# DCC-headlight-V2.net
KiCad netlist of a schematic drawn in EAGLE
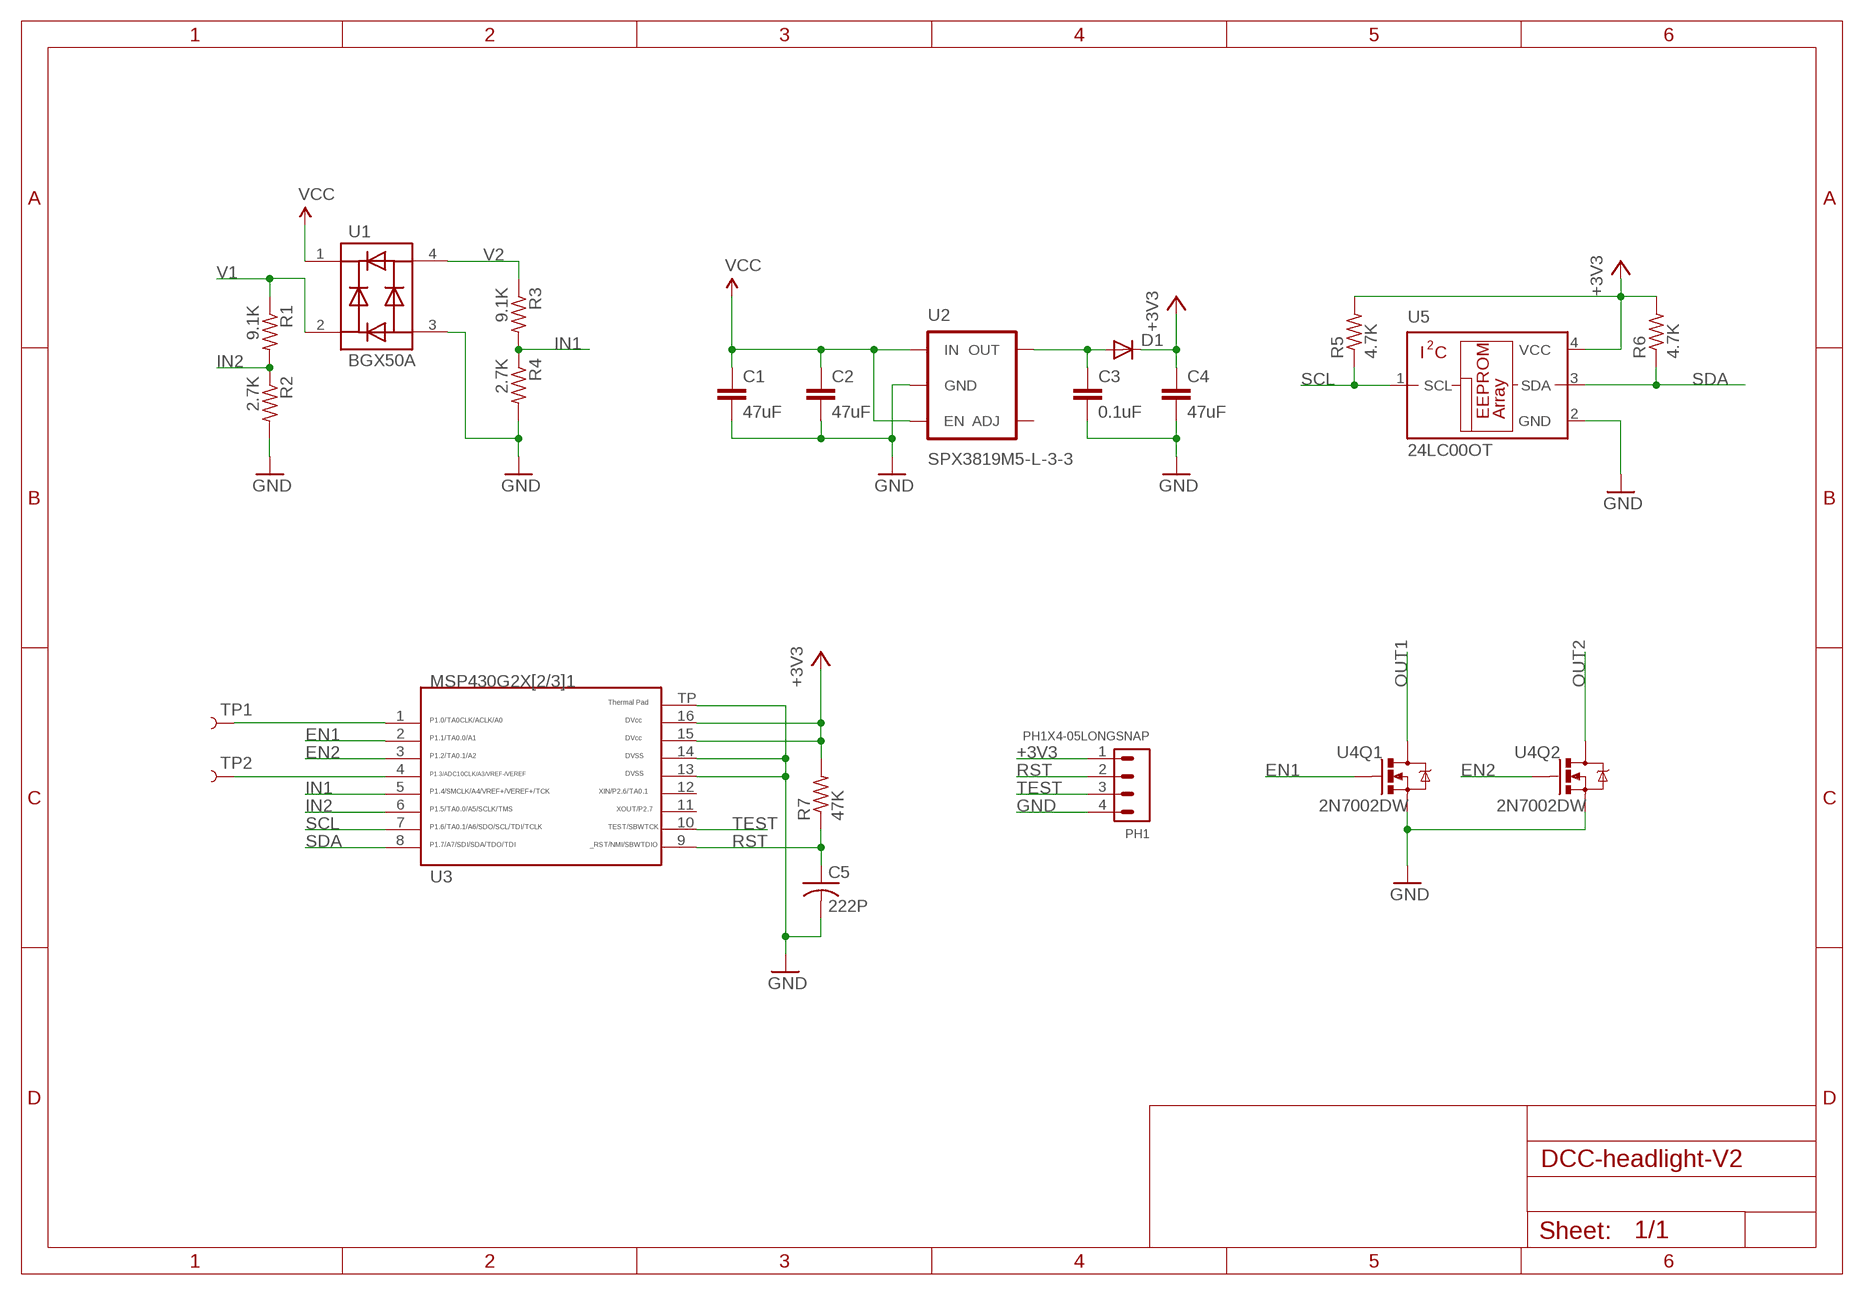
[diagram p0: schematic, sheet 1]

(export (version "E")
  (design (tool "Eeschema 10.0.6"))
  (components
    (comp (ref "C1")
      (value "47uF")
      (footprint "eagle-import:0402-CAP")
      (libsource (lib "eagle-import") (part "CAP0402-CAP"))
    )
    (comp (ref "C2")
      (value "47uF")
      (footprint "eagle-import:0402-CAP")
      (libsource (lib "eagle-import") (part "CAP0402-CAP"))
    )
    (comp (ref "C3")
      (value "0.1uF")
      (footprint "eagle-import:0402-CAP")
      (libsource (lib "eagle-import") (part "CAP0402-CAP"))
    )
    (comp (ref "C4")
      (value "47uF")
      (footprint "eagle-import:0402-CAP")
      (libsource (lib "eagle-import") (part "CAP0402-CAP"))
    )
    (comp (ref "C5")
      (value "222P")
      (footprint "eagle-import:C0402")
      (libsource (lib "eagle-import") (part "C-USC0402"))
    )
    (comp (ref "D1")
      (value "DIODE-SOD523")
      (footprint "eagle-import:SOD523")
      (libsource (lib "eagle-import") (part "DIODE-SOD523"))
    )
    (comp (ref "PH1")
      (value "PH1X4-05LONGSNAP")
      (footprint "eagle-import:PHLS005-1-4")
      (libsource (lib "eagle-import") (part "PH1X4-05LONGSNAP"))
    )
    (comp (ref "R1")
      (value "9.1K")
      (footprint "eagle-import:R0402")
      (libsource (lib "eagle-import") (part "R-US_R0402"))
    )
    (comp (ref "R2")
      (value "2.7K")
      (footprint "eagle-import:R0402")
      (libsource (lib "eagle-import") (part "R-US_R0402"))
    )
    (comp (ref "R3")
      (value "9.1K")
      (footprint "eagle-import:R0402")
      (libsource (lib "eagle-import") (part "R-US_R0402"))
    )
    (comp (ref "R4")
      (value "2.7K")
      (footprint "eagle-import:R0402")
      (libsource (lib "eagle-import") (part "R-US_R0402"))
    )
    (comp (ref "R5")
      (value "4.7K")
      (footprint "eagle-import:R0402")
      (libsource (lib "eagle-import") (part "R-US_R0402"))
    )
    (comp (ref "R6")
      (value "4.7K")
      (footprint "eagle-import:R0402")
      (libsource (lib "eagle-import") (part "R-US_R0402"))
    )
    (comp (ref "R7")
      (value "47K")
      (footprint "eagle-import:R0402")
      (libsource (lib "eagle-import") (part "R-US_R0402"))
    )
    (comp (ref "TP1")
      (value "TEST-POINT3")
      (footprint "eagle-import:PAD.03X.03")
      (libsource (lib "eagle-import") (part "TEST-POINT3"))
    )
    (comp (ref "TP2")
      (value "TEST-POINT3")
      (footprint "eagle-import:PAD.03X.03")
      (libsource (lib "eagle-import") (part "TEST-POINT3"))
    )
    (comp (ref "U1")
      (value "BGX50A")
      (footprint "eagle-import:SOT143")
      (libsource (lib "eagle-import") (part "BGX50A"))
    )
    (comp (ref "U2")
      (value "SPX3819M5-L-3-3")
      (footprint "eagle-import:SOT23-5")
      (libsource (lib "eagle-import") (part "AP2202-ADJ"))
    )
    (comp (ref "U3")
      (value "G2X[2/3]1---RSA16")
      (footprint "eagle-import:RSA16")
      (libsource (lib "eagle-import") (part "G2X[2/3]1---RSA16"))
    )
    (comp (ref "U4")
      (value "2N7002DW")
      (footprint "eagle-import:SOT363")
      (libsource (lib "eagle-import") (part "2N7002DW"))
    )
    (comp (ref "U5")
      (value "24LC00OT")
      (footprint "eagle-import:SOT23-5L")
      (fields (field (name "MF") "MICROCHIP") (field (name "MPN") "24LC00T-I/OT"))
      (libsource (lib "eagle-import") (part "2400OTLC"))
    )
  )
  (nets
    (net (code "1") (name "+3V3") (class "Default")
      (node (ref "C4") (pin "1") (pinfunction "1_1") (pintype "passive"))
      (node (ref "D1") (pin "C") (pinfunction "C_C") (pintype "passive"))
      (node (ref "PH1") (pin "1") (pinfunction "1_1") (pintype "bidirectional"))
      (node (ref "R5") (pin "2") (pinfunction "2_2") (pintype "passive"))
      (node (ref "R6") (pin "2") (pinfunction "2_2") (pintype "passive"))
      (node (ref "R7") (pin "2") (pinfunction "2_2") (pintype "passive"))
      (node (ref "U3") (pin "15") (pinfunction "15_15") (pintype "bidirectional"))
      (node (ref "U3") (pin "16") (pinfunction "16_16") (pintype "bidirectional"))
      (node (ref "U5") (pin "4") (pinfunction "VCC_4") (pintype "power_in"))
    )
    (net (code "2") (name "/EN1") (class "Default")
      (node (ref "U3") (pin "2") (pinfunction "2_2") (pintype "bidirectional"))
      (node (ref "U4") (pin "2") (pinfunction "G_2") (pintype "passive"))
    )
    (net (code "3") (name "/EN2") (class "Default")
      (node (ref "U3") (pin "3") (pinfunction "3_3") (pintype "bidirectional"))
      (node (ref "U4") (pin "5") (pinfunction "G_5") (pintype "passive"))
    )
    (net (code "4") (name "/IN1") (class "Default")
      (node (ref "R3") (pin "2") (pinfunction "2_2") (pintype "passive"))
      (node (ref "R4") (pin "1") (pinfunction "1_1") (pintype "passive"))
      (node (ref "U3") (pin "5") (pinfunction "5_5") (pintype "bidirectional"))
    )
    (net (code "5") (name "/IN2") (class "Default")
      (node (ref "R1") (pin "2") (pinfunction "2_2") (pintype "passive"))
      (node (ref "R2") (pin "1") (pinfunction "1_1") (pintype "passive"))
      (node (ref "U3") (pin "6") (pinfunction "6_6") (pintype "bidirectional"))
    )
    (net (code "6") (name "/OUT1") (class "Default")
      (node (ref "U4") (pin "6") (pinfunction "D_6") (pintype "passive"))
    )
    (net (code "7") (name "/OUT2") (class "Default")
      (node (ref "U4") (pin "3") (pinfunction "D_3") (pintype "passive"))
    )
    (net (code "8") (name "/RST") (class "Default")
      (node (ref "C5") (pin "1") (pinfunction "1_1") (pintype "passive"))
      (node (ref "PH1") (pin "2") (pinfunction "2_2") (pintype "bidirectional"))
      (node (ref "R7") (pin "1") (pinfunction "1_1") (pintype "passive"))
      (node (ref "U3") (pin "9") (pinfunction "9_9") (pintype "bidirectional"))
    )
    (net (code "9") (name "/SCL") (class "Default")
      (node (ref "R5") (pin "1") (pinfunction "1_1") (pintype "passive"))
      (node (ref "U3") (pin "7") (pinfunction "7_7") (pintype "bidirectional"))
      (node (ref "U5") (pin "1") (pinfunction "SCL_1") (pintype "input"))
    )
    (net (code "10") (name "/SDA") (class "Default")
      (node (ref "R6") (pin "1") (pinfunction "1_1") (pintype "passive"))
      (node (ref "U3") (pin "8") (pinfunction "8_8") (pintype "bidirectional"))
      (node (ref "U5") (pin "3") (pinfunction "SDA_3") (pintype "bidirectional"))
    )
    (net (code "11") (name "/TEST") (class "Default")
      (node (ref "PH1") (pin "3") (pinfunction "3_3") (pintype "bidirectional"))
      (node (ref "U3") (pin "10") (pinfunction "10_10") (pintype "bidirectional"))
    )
    (net (code "12") (name "/V1") (class "Default")
      (node (ref "R1") (pin "1") (pinfunction "1_1") (pintype "passive"))
      (node (ref "U1") (pin "2") (pinfunction "2_2") (pintype "bidirectional"))
    )
    (net (code "13") (name "/V2") (class "Default")
      (node (ref "R3") (pin "1") (pinfunction "1_1") (pintype "passive"))
      (node (ref "U1") (pin "4") (pinfunction "4_4") (pintype "bidirectional"))
    )
    (net (code "14") (name "GND") (class "Default")
      (node (ref "C1") (pin "2") (pinfunction "2_2") (pintype "passive"))
      (node (ref "C2") (pin "2") (pinfunction "2_2") (pintype "passive"))
      (node (ref "C3") (pin "2") (pinfunction "2_2") (pintype "passive"))
      (node (ref "C4") (pin "2") (pinfunction "2_2") (pintype "passive"))
      (node (ref "C5") (pin "2") (pinfunction "2_2") (pintype "passive"))
      (node (ref "PH1") (pin "4") (pinfunction "4_4") (pintype "bidirectional"))
      (node (ref "R2") (pin "2") (pinfunction "2_2") (pintype "passive"))
      (node (ref "R4") (pin "2") (pinfunction "2_2") (pintype "passive"))
      (node (ref "U1") (pin "3") (pinfunction "3_3") (pintype "bidirectional"))
      (node (ref "U2") (pin "2") (pinfunction "GND_2") (pintype "input"))
      (node (ref "U3") (pin "13") (pinfunction "13_13") (pintype "bidirectional"))
      (node (ref "U3") (pin "14") (pinfunction "14_14") (pintype "bidirectional"))
      (node (ref "U3") (pin "TP") (pinfunction "TP_TP") (pintype "bidirectional"))
      (node (ref "U4") (pin "1") (pinfunction "S_1") (pintype "passive"))
      (node (ref "U4") (pin "4") (pinfunction "S_4") (pintype "passive"))
      (node (ref "U5") (pin "2") (pinfunction "GND_2") (pintype "power_in"))
    )
    (net (code "15") (name "Net-(TP1-1)") (class "Default")
      (node (ref "TP1") (pin "P$1") (pinfunction "1_P$1") (pintype "bidirectional"))
      (node (ref "U3") (pin "1") (pinfunction "1_1") (pintype "bidirectional"))
    )
    (net (code "16") (name "Net-(TP2-1)") (class "Default")
      (node (ref "TP2") (pin "P$1") (pinfunction "1_P$1") (pintype "bidirectional"))
      (node (ref "U3") (pin "4") (pinfunction "4_4") (pintype "bidirectional"))
    )
    (net (code "17") (name "Net-(U2-OUT)") (class "Default")
      (node (ref "C3") (pin "1") (pinfunction "1_1") (pintype "passive"))
      (node (ref "D1") (pin "A") (pinfunction "A_A") (pintype "passive"))
      (node (ref "U2") (pin "5") (pinfunction "OUT_5") (pintype "passive"))
    )
    (net (code "18") (name "VCC") (class "Default")
      (node (ref "C1") (pin "1") (pinfunction "1_1") (pintype "passive"))
      (node (ref "C2") (pin "1") (pinfunction "1_1") (pintype "passive"))
      (node (ref "U1") (pin "1") (pinfunction "1_1") (pintype "bidirectional"))
      (node (ref "U2") (pin "1") (pinfunction "IN_1") (pintype "input"))
      (node (ref "U2") (pin "3") (pinfunction "EN_3") (pintype "input"))
    )
    (net (code "19") (name "unconnected-(U2-ADJ-Pad4)") (class "Default")
      (node (ref "U2") (pin "4") (pinfunction "ADJ_4") (pintype "input"))
    )
    (net (code "20") (name "unconnected-(U3-Pad11)") (class "Default")
      (node (ref "U3") (pin "11") (pinfunction "11_11") (pintype "bidirectional"))
    )
    (net (code "21") (name "unconnected-(U3-Pad12)") (class "Default")
      (node (ref "U3") (pin "12") (pinfunction "12_12") (pintype "bidirectional"))
    )
  )
)
